# jetson_nano_breakout_rev1.net
KiCad netlist of a schematic drawn in Altium Designer
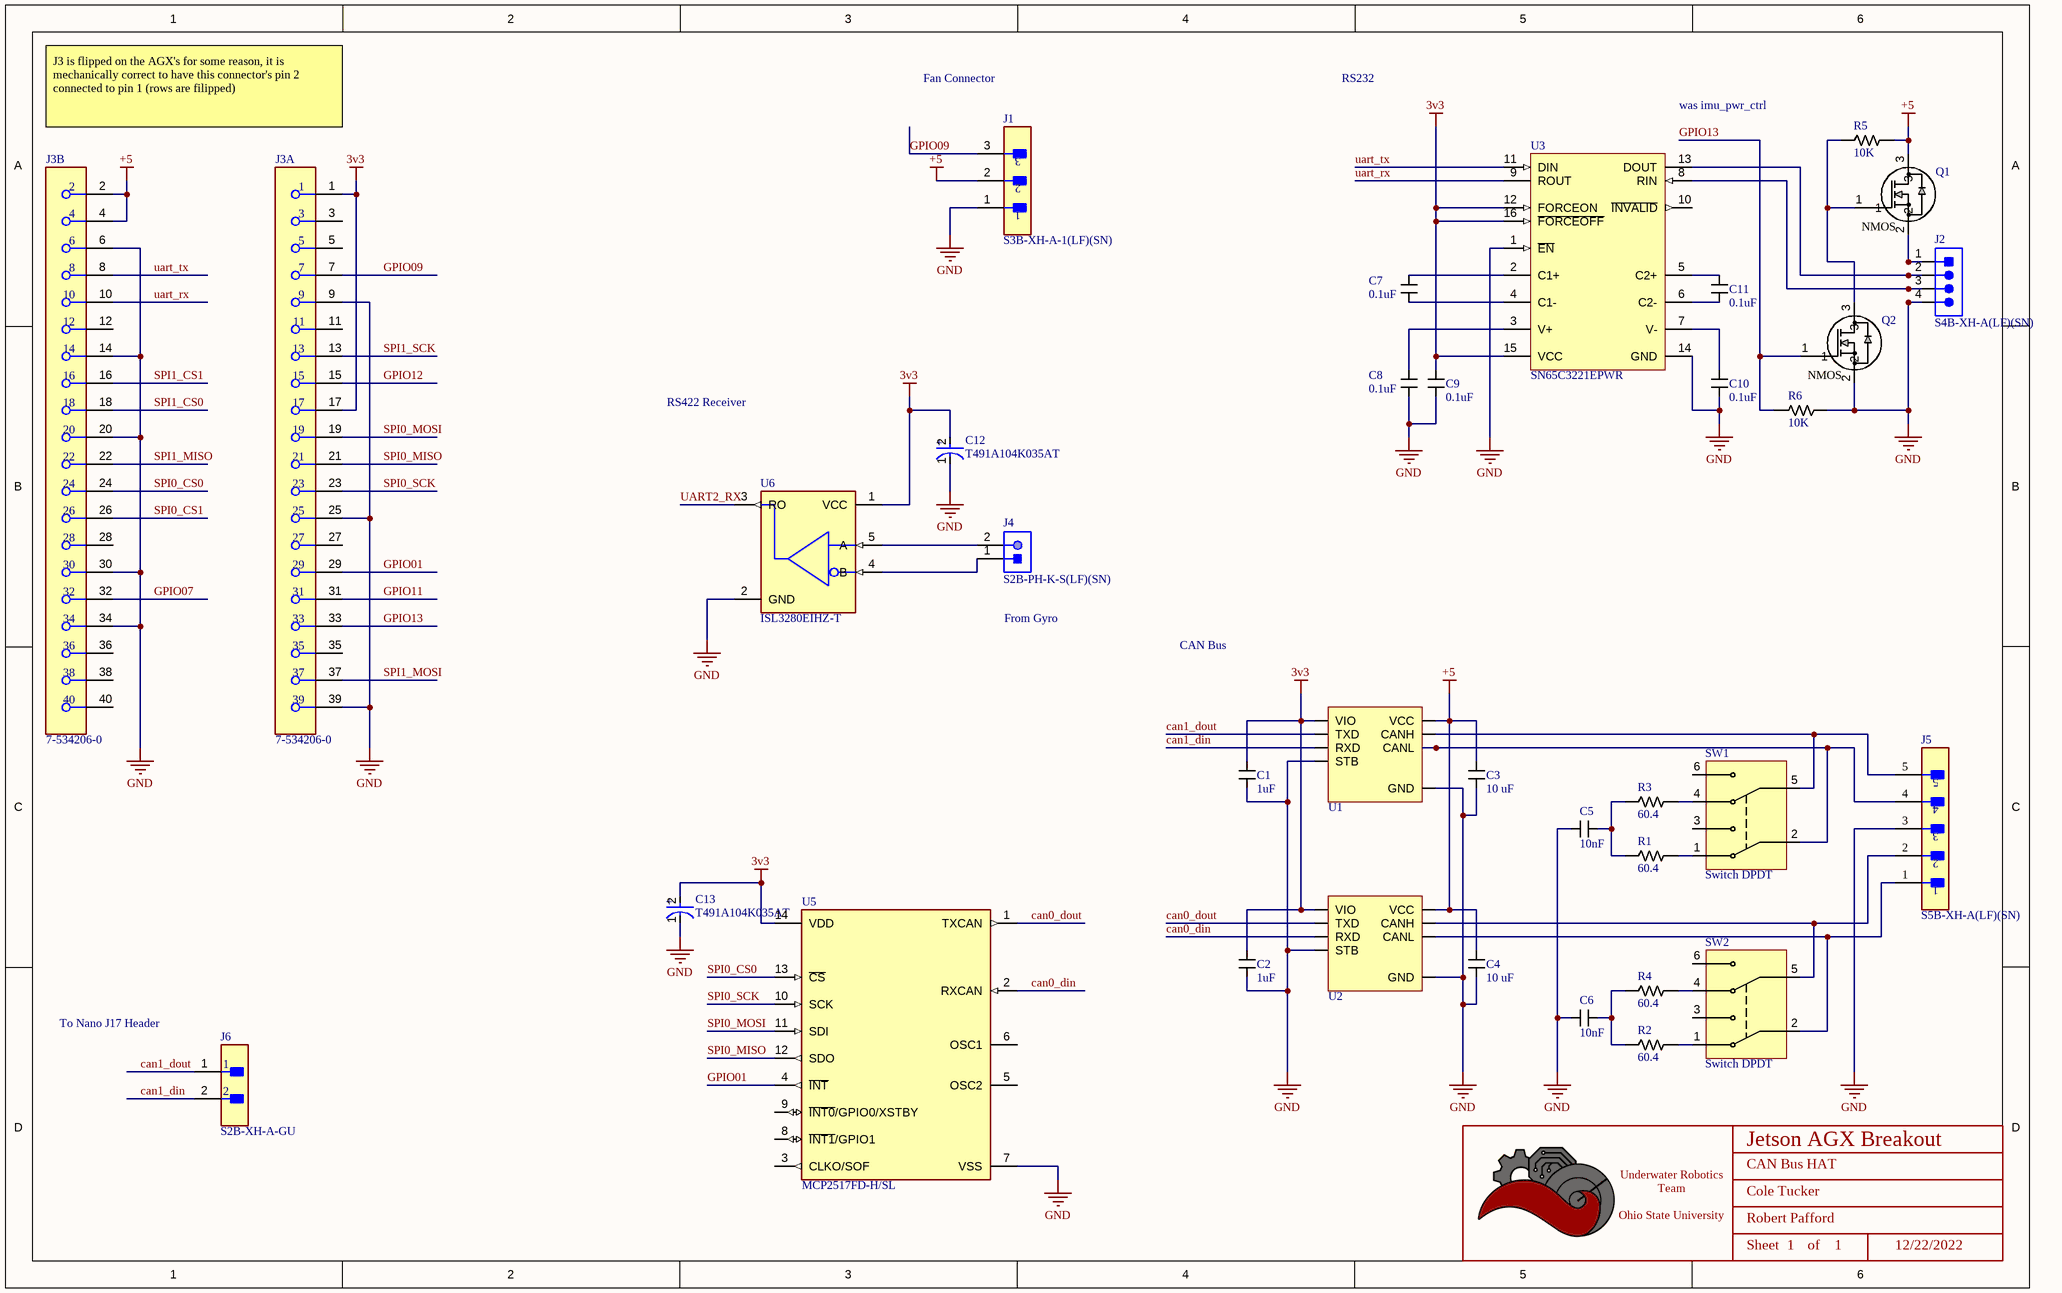
[diagram p0: jetson_nano_breakout_rev1.SchDoc]

(export (version "E")
  (design (tool "Eeschema 10.0.6"))
  (components
    (comp (ref "*")
      (value "Title_Block")
      (footprint "LOGO")
      (description "UWRT Schematic Title Block Template\r\n\r\nCreated June 2021, Dylan Trainor")
      (libsource (lib "UWRT") (part "Title_Block"))
    )
    (comp (ref "C1")
      (value "1uF")
      (footprint "CAPACITOR_0603")
      (description "Cap 1uF 16V +/-10%\r\nCeramic 0603")
      (fields
        (field (name "TOLERANCE") "+/- 10%")
        (field (name "VOLTAGE") "16V")
        (field (name "MADE BY") "Flip B")
      )
      (libsource (lib "Capacitors") (part "CAPACITOR_1uF_0603"))
    )
    (comp (ref "C2")
      (value "1uF")
      (footprint "CAPACITOR_0603")
      (description "Cap 1uF 16V +/-10%\r\nCeramic 0603")
      (fields
        (field (name "TOLERANCE") "+/- 10%")
        (field (name "VOLTAGE") "16V")
        (field (name "MADE BY") "Flip B")
      )
      (libsource (lib "Capacitors") (part "CAPACITOR_1uF_0603"))
    )
    (comp (ref "C3")
      (value "10uF Ceramic 6.3V")
      (footprint "CAPACITOR_0603")
      (description "Cap 10uF 6.3V +/-20%\r\nCeramic 0603")
      (fields
        (field (name "TOLERANCE") "+/- 20%")
        (field (name "VOLTAGE") "6.3V")
        (field (name "VALUE (UF)") "10 uF")
        (field (name "MADE BY") "Flip B")
      )
      (libsource (lib "Capacitors") (part "CAPACITOR_10uF_0603"))
    )
    (comp (ref "C4")
      (value "10uF Ceramic 6.3V")
      (footprint "CAPACITOR_0603")
      (description "Cap 10uF 6.3V +/-20%\r\nCeramic 0603")
      (fields
        (field (name "TOLERANCE") "+/- 20%")
        (field (name "VOLTAGE") "6.3V")
        (field (name "VALUE (UF)") "10 uF")
        (field (name "MADE BY") "Flip B")
      )
      (libsource (lib "Capacitors") (part "CAPACITOR_10uF_0603"))
    )
    (comp (ref "C5")
      (value "10nF")
      (footprint "CAPACITOR_0603")
      (description "Cap 10nF 6.3V +/-20%\r\nCeramic 0603")
      (fields
        (field (name "TOLERANCE") "+/- 10%")
        (field (name "VOLTAGE") "6.3V")
        (field (name "MADE BY") "Flip B")
      )
      (libsource (lib "Capacitors") (part "CAPACITOR_0.01uF_0603"))
    )
    (comp (ref "C6")
      (value "10nF")
      (footprint "CAPACITOR_0603")
      (description "Cap 10nF 6.3V +/-20%\r\nCeramic 0603")
      (fields
        (field (name "TOLERANCE") "+/- 10%")
        (field (name "VOLTAGE") "6.3V")
        (field (name "MADE BY") "Flip B")
      )
      (libsource (lib "Capacitors") (part "CAPACITOR_0.01uF_0603"))
    )
    (comp (ref "C7")
      (value "0.1uF")
      (footprint "CAPACITOR_0603")
      (description "Cap 100nF 6.3V +/-10%\r\nCeramic 0603")
      (fields
        (field (name "TOLERANCE") "+/- 10%")
        (field (name "VOLTAGE") "6.3V")
        (field (name "MADE BY") "Flip B")
      )
      (libsource (lib "Capacitors") (part "CAPACITOR_0.1uF_0603"))
    )
    (comp (ref "C8")
      (value "0.1uF")
      (footprint "CAPACITOR_0603")
      (description "Cap 100nF 6.3V +/-10%\r\nCeramic 0603")
      (fields
        (field (name "TOLERANCE") "+/- 10%")
        (field (name "VOLTAGE") "6.3V")
        (field (name "MADE BY") "Flip B")
      )
      (libsource (lib "Capacitors") (part "CAPACITOR_0.1uF_0603"))
    )
    (comp (ref "C9")
      (value "0.1uF")
      (footprint "CAPACITOR_0603")
      (description "Cap 100nF 6.3V +/-10%\r\nCeramic 0603")
      (fields
        (field (name "TOLERANCE") "+/- 10%")
        (field (name "VOLTAGE") "6.3V")
        (field (name "MADE BY") "Flip B")
      )
      (libsource (lib "Capacitors") (part "CAPACITOR_0.1uF_0603"))
    )
    (comp (ref "C10")
      (value "0.1uF")
      (footprint "CAPACITOR_0603")
      (description "Cap 100nF 6.3V +/-10%\r\nCeramic 0603")
      (fields
        (field (name "TOLERANCE") "+/- 10%")
        (field (name "VOLTAGE") "6.3V")
        (field (name "MADE BY") "Flip B")
      )
      (libsource (lib "Capacitors") (part "CAPACITOR_0.1uF_0603"))
    )
    (comp (ref "C11")
      (value "0.1uF")
      (footprint "CAPACITOR_0603")
      (description "Cap 100nF 6.3V +/-10%\r\nCeramic 0603")
      (fields
        (field (name "TOLERANCE") "+/- 10%")
        (field (name "VOLTAGE") "6.3V")
        (field (name "MADE BY") "Flip B")
      )
      (libsource (lib "Capacitors") (part "CAPACITOR_0.1uF_0603"))
    )
    (comp (ref "C12")
      (value "T491A104K035AT")
      (footprint "FP-T491A104K035AT-MFG")
      (description "CAP TANT 0.1UF 10% 35V 1206")
      (fields (field (name "TOLERANCE") "10%") (field (name "VOLTAGE") "35V"))
      (libsource (lib "Altium Content Vault") (part "a00bbbee19879c290e62620ae7e47b1"))
    )
    (comp (ref "C13")
      (value "T491A104K035AT")
      (footprint "FP-T491A104K035AT-MFG")
      (description "CAP TANT 0.1UF 10% 35V 1206")
      (fields (field (name "TOLERANCE") "10%") (field (name "VOLTAGE") "35V"))
      (libsource (lib "Altium Content Vault") (part "a00bbbee19879c290e62620ae7e47b1"))
    )
    (comp (ref "J1")
      (value "S3B-XH-A-1(LF)(SN)")
      (footprint "FP-S3B-XH-A-1_LF_SN-MFG")
      (description "CONN HEADER R/A 3POS 2.5MM")
      (libsource (lib "Altium Content Vault") (part "0d3f023dd272f625e17a2be33dea85f"))
    )
    (comp (ref "J2")
      (value "S4B-XH-A(LF)(SN)")
      (footprint "JST-S4B-XH-A(LF)(SN)_V")
      (libsource (lib "Altium Content Vault") (part "CN-1P-M-R4"))
    )
    (comp (ref "J3")
      (value "7-534206-0")
      (footprint "FP-7-534206-0-MFG")
      (description "CONN RCPT 40POS 0.1 GOLD PCB")
      (fields
        (field (name "MANUFACTURER") "TE Connectivity")
        (field (name "OCTOPART") "https://octopart.com/7-534206-0-te+connectivity-39516831")
      )
      (libsource (lib "Altium Content Vault") (part "7acf1c4a8db21028d11741a46a6ec78"))
    )
    (comp (ref "J4")
      (value "S2B-PH-K-S(LF)(SN)")
      (footprint "JST-S2B-PH-K-S_V")
      (fields (field (name "TOLERANCE") "20%"))
      (libsource (lib "Altium Content Vault") (part "CN-1P-M-R2"))
    )
    (comp (ref "J5")
      (value "S5B-XH-A(LF)(SN)")
      (footprint "FP-S5B-XH-A_LF_SN-MFG")
      (description "CONN HEADER R/A 5POS 2.5MM")
      (libsource (lib "Altium Content Vault") (part "bf93c07fd2649a848d0ec8585582aab"))
    )
    (comp (ref "J6")
      (value "S2B-XH-A-GU")
      (footprint "FP-S2B-XH-A-GU-MFG")
      (description "Conn Shrouded Header HDR 2 POS 2.45mm Solder ST Top Entry Thru-Hole")
      (libsource (lib "Altium Content Vault") (part "3bc925449376181038e59eaffc5286c"))
    )
    (comp (ref "Q1")
      (value "MOSFET N-CH 30V 5.8A SOT-23-3")
      (footprint "SOT-23-3")
      (description "N-Channel 30 V 5.8A (Ta) 1.4W (Ta) Surface Mount SOT-23-3")
      (fields (field (name "MANUFACTURER _PART_NUMBER") "AO3404A") (field (name "CREATED BY") "Dylan T"))
      (libsource (lib "Transistors") (part "AO3404A"))
    )
    (comp (ref "Q2")
      (value "MOSFET N-CH 30V 5.8A SOT-23-3")
      (footprint "SOT-23-3")
      (description "N-Channel 30 V 5.8A (Ta) 1.4W (Ta) Surface Mount SOT-23-3")
      (fields (field (name "MANUFACTURER _PART_NUMBER") "AO3404A") (field (name "CREATED BY") "Dylan T"))
      (libsource (lib "Transistors") (part "AO3404A"))
    )
    (comp (ref "R1")
      (value "60.4 Ohm 1% 1/16W")
      (footprint "RESISTOR_0402")
      (description "RES 60.4 OHM 1% 1/16W 0402")
      (fields
        (field (name "TOLERANCE") "+/- 1%")
        (field (name "VALUE  (OHMS)") "60.4")
        (field (name "MADE BY") "Robert Pafford")
      )
      (libsource (lib "Resistors") (part "RESISTOR_60.4_0402"))
    )
    (comp (ref "R2")
      (value "60.4 Ohm 1% 1/16W")
      (footprint "RESISTOR_0402")
      (description "RES 60.4 OHM 1% 1/16W 0402")
      (fields
        (field (name "TOLERANCE") "+/- 1%")
        (field (name "VALUE  (OHMS)") "60.4")
        (field (name "MADE BY") "Robert Pafford")
      )
      (libsource (lib "Resistors") (part "RESISTOR_60.4_0402"))
    )
    (comp (ref "R3")
      (value "60.4 Ohm 1% 1/16W")
      (footprint "RESISTOR_0402")
      (description "RES 60.4 OHM 1% 1/16W 0402")
      (fields
        (field (name "TOLERANCE") "+/- 1%")
        (field (name "VALUE  (OHMS)") "60.4")
        (field (name "MADE BY") "Robert Pafford")
      )
      (libsource (lib "Resistors") (part "RESISTOR_60.4_0402"))
    )
    (comp (ref "R4")
      (value "60.4 Ohm 1% 1/16W")
      (footprint "RESISTOR_0402")
      (description "RES 60.4 OHM 1% 1/16W 0402")
      (fields
        (field (name "TOLERANCE") "+/- 1%")
        (field (name "VALUE  (OHMS)") "60.4")
        (field (name "MADE BY") "Robert Pafford")
      )
      (libsource (lib "Resistors") (part "RESISTOR_60.4_0402"))
    )
    (comp (ref "R5")
      (value "10k Ohm 5% 1/10W")
      (footprint "RESISTOR_0603")
      (description "RES 10k OHM 5% 1/10W 0603")
      (fields
        (field (name "TOLERANCE") "+/- 5%")
        (field (name "VALUE  (OHMS)") "10K")
        (field (name "MADE BY") "Robert Pafford")
      )
      (libsource (lib "Resistors") (part "RESISTOR_10K_0603"))
    )
    (comp (ref "R6")
      (value "10k Ohm 5% 1/10W")
      (footprint "RESISTOR_0603")
      (description "RES 10k OHM 5% 1/10W 0603")
      (fields
        (field (name "TOLERANCE") "+/- 5%")
        (field (name "VALUE  (OHMS)") "10K")
        (field (name "MADE BY") "Robert Pafford")
      )
      (libsource (lib "Resistors") (part "RESISTOR_10K_0603"))
    )
    (comp (ref "SW1")
      (value "Switch DPDT")
      (footprint "CAS-220TA")
      (description "GOLD SWITCH FLUSH SLIDE DPDT 100MA 6V")
      (fields (field (name "MADE BY") "Robert Pafford"))
      (libsource (lib "Switches") (part "CAS-220TA_CAN_TERM"))
    )
    (comp (ref "SW2")
      (value "Switch DPDT")
      (footprint "CAS-220TA")
      (description "GOLD SWITCH FLUSH SLIDE DPDT 100MA 6V")
      (fields (field (name "MADE BY") "Robert Pafford"))
      (libsource (lib "Switches") (part "CAS-220TA_CAN_TERM"))
    )
    (comp (ref "U1")
      (value "CAN Transceiver")
      (footprint "SOIC-8")
      (description "CAN Interface IC High-Speed CAN Transceiver with Standby Mode")
      (fields (field (name "MADE BY") "Robert Pafford"))
      (libsource (lib "Integrated Circuits") (part "TJA1442AT"))
    )
    (comp (ref "U2")
      (value "CAN Transceiver")
      (footprint "SOIC-8")
      (description "CAN Interface IC High-Speed CAN Transceiver with Standby Mode")
      (fields (field (name "MADE BY") "Robert Pafford"))
      (libsource (lib "Integrated Circuits") (part "TJA1442AT"))
    )
    (comp (ref "U3")
      (value "SN65C3221EPWR")
      (footprint "PW0016A_M")
      (libsource (lib "Altium Content Vault") (part "TI-SN65C3221E-TSSOP_PW-16"))
    )
    (comp (ref "U5")
      (value "MCP2517FD-H/SL")
      (footprint "FP-C04-065-SL-MFG")
      (description "IC CANBUS CONTROLLER SPI 14SOIC")
      (fields
        (field (name "MANUFACTURER") "Microchip")
        (field (name "OCTOPART") "https://octopart.com/mcp2517fd-h%2Fsl-microchip-83497369")
      )
      (libsource (lib "Altium Content Vault") (part "008caafe10a874835a82fe443bcfa61"))
    )
    (comp (ref "U6")
      (value "ISL3280EIHZ-T")
      (footprint "FP-P5_064-MFG")
      (description "IC RCVR ESD RS485/422 LP SOT23-5")
      (fields
        (field (name "MANUFACTURER") "Renesas")
        (field (name "OCTOPART") "https://octopart.com/isl3280eihz-t-renesas-88254858")
      )
      (libsource (lib "Altium Content Vault") (part "dfcd02365d4109d45b3bc98e27c58b4"))
    )
  )
  (nets
    (net (code "1") (name "+5") (class "Default")
      (node (ref "C3") (pin "1") (pinfunction "1_1") (pintype "passive"))
      (node (ref "C4") (pin "1") (pinfunction "1_1") (pintype "passive"))
      (node (ref "J1") (pin "2") (pinfunction "2_2") (pintype "passive"))
      (node (ref "J3") (pin "2") (pinfunction "2_2") (pintype "passive"))
      (node (ref "J3") (pin "4") (pinfunction "4_4") (pintype "passive"))
      (node (ref "Q1") (pin "3") (pinfunction "3_3") (pintype "passive"))
      (node (ref "R5") (pin "1") (pinfunction "1_1") (pintype "passive"))
      (node (ref "U1") (pin "3") (pinfunction "VCC_3") (pintype "passive"))
      (node (ref "U2") (pin "3") (pinfunction "VCC_3") (pintype "passive"))
    )
    (net (code "2") (name "/GPIO01") (class "Default")
      (node (ref "J3") (pin "29") (pinfunction "29_29") (pintype "passive"))
      (node (ref "U5") (pin "4") (pinfunction "~{INT}_4") (pintype "output"))
    )
    (net (code "3") (name "/GPIO07") (class "Default")
      (node (ref "J3") (pin "32") (pinfunction "32_32") (pintype "passive"))
    )
    (net (code "4") (name "/GPIO09") (class "Default")
      (node (ref "J1") (pin "3") (pinfunction "3_3") (pintype "passive"))
      (node (ref "J3") (pin "7") (pinfunction "7_7") (pintype "passive"))
    )
    (net (code "5") (name "/GPIO11") (class "Default")
      (node (ref "J3") (pin "31") (pinfunction "31_31") (pintype "passive"))
    )
    (net (code "6") (name "/GPIO12") (class "Default")
      (node (ref "J3") (pin "15") (pinfunction "15_15") (pintype "passive"))
    )
    (net (code "7") (name "/GPIO13") (class "Default")
      (node (ref "J3") (pin "33") (pinfunction "33_33") (pintype "passive"))
      (node (ref "Q2") (pin "1") (pinfunction "1_1") (pintype "passive"))
      (node (ref "R6") (pin "1") (pinfunction "1_1") (pintype "passive"))
    )
    (net (code "8") (name "/SPI0_CS0") (class "Default")
      (node (ref "J3") (pin "24") (pinfunction "24_24") (pintype "passive"))
      (node (ref "U5") (pin "13") (pinfunction "~{CS}_13") (pintype "input"))
    )
    (net (code "9") (name "/SPI0_CS1") (class "Default")
      (node (ref "J3") (pin "26") (pinfunction "26_26") (pintype "passive"))
    )
    (net (code "10") (name "/SPI0_MISO") (class "Default")
      (node (ref "J3") (pin "21") (pinfunction "21_21") (pintype "passive"))
      (node (ref "U5") (pin "12") (pinfunction "SDO_12") (pintype "output"))
    )
    (net (code "11") (name "/SPI0_MOSI") (class "Default")
      (node (ref "J3") (pin "19") (pinfunction "19_19") (pintype "passive"))
      (node (ref "U5") (pin "11") (pinfunction "SDI_11") (pintype "input"))
    )
    (net (code "12") (name "/SPI0_SCK") (class "Default")
      (node (ref "J3") (pin "23") (pinfunction "23_23") (pintype "passive"))
      (node (ref "U5") (pin "10") (pinfunction "SCK_10") (pintype "input"))
    )
    (net (code "13") (name "/SPI1_CS0") (class "Default")
      (node (ref "J3") (pin "18") (pinfunction "18_18") (pintype "passive"))
    )
    (net (code "14") (name "/SPI1_CS1") (class "Default")
      (node (ref "J3") (pin "16") (pinfunction "16_16") (pintype "passive"))
    )
    (net (code "15") (name "/SPI1_MISO") (class "Default")
      (node (ref "J3") (pin "22") (pinfunction "22_22") (pintype "passive"))
    )
    (net (code "16") (name "/SPI1_MOSI") (class "Default")
      (node (ref "J3") (pin "37") (pinfunction "37_37") (pintype "passive"))
    )
    (net (code "17") (name "/SPI1_SCK") (class "Default")
      (node (ref "J3") (pin "13") (pinfunction "13_13") (pintype "passive"))
    )
    (net (code "18") (name "/UART2_RX") (class "Default")
      (node (ref "U6") (pin "3") (pinfunction "RO_3") (pintype "output"))
    )
    (net (code "19") (name "/can0_din") (class "Default")
      (node (ref "U2") (pin "4") (pinfunction "RXD_4") (pintype "passive"))
      (node (ref "U5") (pin "2") (pinfunction "RXCAN_2") (pintype "input"))
    )
    (net (code "20") (name "/can0_dout") (class "Default")
      (node (ref "U2") (pin "1") (pinfunction "TXD_1") (pintype "passive"))
      (node (ref "U5") (pin "1") (pinfunction "TXCAN_1") (pintype "output"))
    )
    (net (code "21") (name "/can1_din") (class "Default")
      (node (ref "J6") (pin "2") (pinfunction "2_2") (pintype "passive"))
      (node (ref "U1") (pin "4") (pinfunction "RXD_4") (pintype "passive"))
    )
    (net (code "22") (name "/can1_dout") (class "Default")
      (node (ref "J6") (pin "1") (pinfunction "1_1") (pintype "passive"))
      (node (ref "U1") (pin "1") (pinfunction "TXD_1") (pintype "passive"))
    )
    (net (code "23") (name "/uart_rx") (class "Default")
      (node (ref "J3") (pin "10") (pinfunction "10_10") (pintype "passive"))
      (node (ref "U3") (pin "9") (pinfunction "ROUT_9") (pintype "tri_state"))
    )
    (net (code "24") (name "/uart_tx") (class "Default")
      (node (ref "J3") (pin "8") (pinfunction "8_8") (pintype "passive"))
      (node (ref "U3") (pin "11") (pinfunction "DIN_11") (pintype "input"))
    )
    (net (code "25") (name "3v3") (class "Default")
      (node (ref "C1") (pin "1") (pinfunction "1_1") (pintype "passive"))
      (node (ref "C12") (pin "2") (pinfunction "A_2") (pintype "passive"))
      (node (ref "C13") (pin "2") (pinfunction "A_2") (pintype "passive"))
      (node (ref "C2") (pin "1") (pinfunction "1_1") (pintype "passive"))
      (node (ref "C9") (pin "1") (pinfunction "1_1") (pintype "passive"))
      (node (ref "J3") (pin "1") (pinfunction "1_1") (pintype "passive"))
      (node (ref "J3") (pin "17") (pinfunction "17_17") (pintype "passive"))
      (node (ref "U1") (pin "5") (pinfunction "VIO_5") (pintype "passive"))
      (node (ref "U2") (pin "5") (pinfunction "VIO_5") (pintype "passive"))
      (node (ref "U3") (pin "12") (pinfunction "FORCEON_12") (pintype "input"))
      (node (ref "U3") (pin "15") (pinfunction "VCC_15") (pintype "power_in"))
      (node (ref "U3") (pin "16") (pinfunction "~{FORCEOFF}_16") (pintype "input"))
      (node (ref "U5") (pin "14") (pinfunction "VDD_14") (pintype "power_in"))
      (node (ref "U6") (pin "1") (pinfunction "VCC_1") (pintype "power_in"))
    )
    (net (code "26") (name "GND") (class "Default")
      (node (ref "C1") (pin "2") (pinfunction "2_2") (pintype "passive"))
      (node (ref "C10") (pin "2") (pinfunction "2_2") (pintype "passive"))
      (node (ref "C12") (pin "1") (pinfunction "C_1") (pintype "passive"))
      (node (ref "C13") (pin "1") (pinfunction "C_1") (pintype "passive"))
      (node (ref "C2") (pin "2") (pinfunction "2_2") (pintype "passive"))
      (node (ref "C3") (pin "2") (pinfunction "2_2") (pintype "passive"))
      (node (ref "C4") (pin "2") (pinfunction "2_2") (pintype "passive"))
      (node (ref "C5") (pin "1") (pinfunction "1_1") (pintype "passive"))
      (node (ref "C6") (pin "1") (pinfunction "1_1") (pintype "passive"))
      (node (ref "C8") (pin "2") (pinfunction "2_2") (pintype "passive"))
      (node (ref "C9") (pin "2") (pinfunction "2_2") (pintype "passive"))
      (node (ref "J1") (pin "1") (pinfunction "1_1") (pintype "passive"))
      (node (ref "J2") (pin "4") (pinfunction "4_4") (pintype "passive"))
      (node (ref "J3") (pin "14") (pinfunction "14_14") (pintype "passive"))
      (node (ref "J3") (pin "20") (pinfunction "20_20") (pintype "passive"))
      (node (ref "J3") (pin "25") (pinfunction "25_25") (pintype "passive"))
      (node (ref "J3") (pin "30") (pinfunction "30_30") (pintype "passive"))
      (node (ref "J3") (pin "34") (pinfunction "34_34") (pintype "passive"))
      (node (ref "J3") (pin "39") (pinfunction "39_39") (pintype "passive"))
      (node (ref "J3") (pin "6") (pinfunction "6_6") (pintype "passive"))
      (node (ref "J3") (pin "9") (pinfunction "9_9") (pintype "passive"))
      (node (ref "J5") (pin "3") (pinfunction "3_3") (pintype "passive"))
      (node (ref "Q2") (pin "2") (pinfunction "2_2") (pintype "passive"))
      (node (ref "R6") (pin "2") (pinfunction "2_2") (pintype "passive"))
      (node (ref "U1") (pin "2") (pinfunction "GND_2") (pintype "passive"))
      (node (ref "U1") (pin "8") (pinfunction "STB_8") (pintype "passive"))
      (node (ref "U2") (pin "2") (pinfunction "GND_2") (pintype "passive"))
      (node (ref "U2") (pin "8") (pinfunction "STB_8") (pintype "passive"))
      (node (ref "U3") (pin "1") (pinfunction "~{EN}_1") (pintype "input"))
      (node (ref "U3") (pin "14") (pinfunction "GND_14") (pintype "power_in"))
      (node (ref "U5") (pin "7") (pinfunction "VSS_7") (pintype "power_in"))
      (node (ref "U6") (pin "2") (pinfunction "GND_2") (pintype "power_in"))
    )
    (net (code "27") (name "Net-(C5-Pad2)") (class "Default")
      (node (ref "C5") (pin "2") (pinfunction "2_2") (pintype "passive"))
      (node (ref "R1") (pin "2") (pinfunction "2_2") (pintype "passive"))
      (node (ref "R3") (pin "2") (pinfunction "2_2") (pintype "passive"))
    )
    (net (code "28") (name "Net-(C6-Pad2)") (class "Default")
      (node (ref "C6") (pin "2") (pinfunction "2_2") (pintype "passive"))
      (node (ref "R2") (pin "2") (pinfunction "2_2") (pintype "passive"))
      (node (ref "R4") (pin "2") (pinfunction "2_2") (pintype "passive"))
    )
    (net (code "29") (name "Net-(J2-Pad1)") (class "Default")
      (node (ref "J2") (pin "1") (pinfunction "1_1") (pintype "passive"))
      (node (ref "Q1") (pin "2") (pinfunction "2_2") (pintype "passive"))
    )
    (net (code "30") (name "Net-(Q1-Pad1)") (class "Default")
      (node (ref "Q1") (pin "1") (pinfunction "1_1") (pintype "passive"))
      (node (ref "Q2") (pin "3") (pinfunction "3_3") (pintype "passive"))
      (node (ref "R5") (pin "2") (pinfunction "2_2") (pintype "passive"))
    )
    (net (code "31") (name "Net-(R1-Pad1)") (class "Default")
      (node (ref "R1") (pin "1") (pinfunction "1_1") (pintype "passive"))
      (node (ref "SW1") (pin "1") (pintype "passive"))
    )
    (net (code "32") (name "Net-(R2-Pad1)") (class "Default")
      (node (ref "R2") (pin "1") (pinfunction "1_1") (pintype "passive"))
      (node (ref "SW2") (pin "1") (pintype "passive"))
    )
    (net (code "33") (name "Net-(R3-Pad1)") (class "Default")
      (node (ref "R3") (pin "1") (pinfunction "1_1") (pintype "passive"))
      (node (ref "SW1") (pin "4") (pintype "passive"))
    )
    (net (code "34") (name "Net-(R4-Pad1)") (class "Default")
      (node (ref "R4") (pin "1") (pinfunction "1_1") (pintype "passive"))
      (node (ref "SW2") (pin "4") (pintype "passive"))
    )
    (net (code "35") (name "Net-(U1-CANH)") (class "Default")
      (node (ref "J5") (pin "5") (pinfunction "5_5") (pintype "passive"))
      (node (ref "SW1") (pin "5") (pintype "passive"))
      (node (ref "U1") (pin "7") (pinfunction "CANH_7") (pintype "passive"))
    )
    (net (code "36") (name "Net-(U1-CANL)") (class "Default")
      (node (ref "J5") (pin "4") (pinfunction "4_4") (pintype "passive"))
      (node (ref "SW1") (pin "2") (pintype "passive"))
      (node (ref "U1") (pin "6") (pinfunction "CANL_6") (pintype "passive"))
    )
    (net (code "37") (name "Net-(U2-CANH)") (class "Default")
      (node (ref "J5") (pin "2") (pinfunction "2_2") (pintype "passive"))
      (node (ref "SW2") (pin "5") (pintype "passive"))
      (node (ref "U2") (pin "7") (pinfunction "CANH_7") (pintype "passive"))
    )
    (net (code "38") (name "Net-(U2-CANL)") (class "Default")
      (node (ref "J5") (pin "1") (pinfunction "1_1") (pintype "passive"))
      (node (ref "SW2") (pin "2") (pintype "passive"))
      (node (ref "U2") (pin "6") (pinfunction "CANL_6") (pintype "passive"))
    )
    (net (code "39") (name "Net-(U3-C1+)") (class "Default")
      (node (ref "C7") (pin "1") (pinfunction "1_1") (pintype "passive"))
      (node (ref "U3") (pin "2") (pinfunction "C1+_2") (pintype "passive"))
    )
    (net (code "40") (name "Net-(U3-C1-)") (class "Default")
      (node (ref "C7") (pin "2") (pinfunction "2_2") (pintype "passive"))
      (node (ref "U3") (pin "4") (pinfunction "C1-_4") (pintype "passive"))
    )
    (net (code "41") (name "Net-(U3-C2+)") (class "Default")
      (node (ref "C11") (pin "1") (pinfunction "1_1") (pintype "passive"))
      (node (ref "U3") (pin "5") (pinfunction "C2+_5") (pintype "passive"))
    )
    (net (code "42") (name "Net-(U3-C2-)") (class "Default")
      (node (ref "C11") (pin "2") (pinfunction "2_2") (pintype "passive"))
      (node (ref "U3") (pin "6") (pinfunction "C2-_6") (pintype "passive"))
    )
    (net (code "43") (name "Net-(U3-DOUT)") (class "Default")
      (node (ref "J2") (pin "2") (pinfunction "2_2") (pintype "passive"))
      (node (ref "U3") (pin "13") (pinfunction "DOUT_13") (pintype "tri_state"))
    )
    (net (code "44") (name "Net-(U3-RIN)") (class "Default")
      (node (ref "J2") (pin "3") (pinfunction "3_3") (pintype "passive"))
      (node (ref "U3") (pin "8") (pinfunction "RIN_8") (pintype "input"))
    )
    (net (code "45") (name "Net-(U3-V+)") (class "Default")
      (node (ref "C8") (pin "1") (pinfunction "1_1") (pintype "passive"))
      (node (ref "U3") (pin "3") (pinfunction "V+_3") (pintype "power_in"))
    )
    (net (code "46") (name "Net-(U3-V-)") (class "Default")
      (node (ref "C10") (pin "1") (pinfunction "1_1") (pintype "passive"))
      (node (ref "U3") (pin "7") (pinfunction "V-_7") (pintype "power_in"))
    )
    (net (code "47") (name "Net-(U6-A)") (class "Default")
      (node (ref "J4") (pin "2") (pinfunction "2_2") (pintype "passive"))
      (node (ref "U6") (pin "5") (pinfunction "A_5") (pintype "input"))
    )
    (net (code "48") (name "Net-(U6-B)") (class "Default")
      (node (ref "J4") (pin "1") (pinfunction "1_1") (pintype "passive"))
      (node (ref "U6") (pin "4") (pinfunction "B_4") (pintype "input"))
    )
    (net (code "49") (name "unconnected-(J3-Pad3)") (class "Default")
      (node (ref "J3") (pin "3") (pinfunction "3_3") (pintype "passive"))
    )
    (net (code "50") (name "unconnected-(J3-Pad5)") (class "Default")
      (node (ref "J3") (pin "5") (pinfunction "5_5") (pintype "passive"))
    )
    (net (code "51") (name "unconnected-(J3-Pad11)") (class "Default")
      (node (ref "J3") (pin "11") (pinfunction "11_11") (pintype "passive"))
    )
    (net (code "52") (name "unconnected-(J3-Pad12)") (class "Default")
      (node (ref "J3") (pin "12") (pinfunction "12_12") (pintype "passive"))
    )
    (net (code "53") (name "unconnected-(J3-Pad27)") (class "Default")
      (node (ref "J3") (pin "27") (pinfunction "27_27") (pintype "passive"))
    )
    (net (code "54") (name "unconnected-(J3-Pad28)") (class "Default")
      (node (ref "J3") (pin "28") (pinfunction "28_28") (pintype "passive"))
    )
    (net (code "55") (name "unconnected-(J3-Pad35)") (class "Default")
      (node (ref "J3") (pin "35") (pinfunction "35_35") (pintype "passive"))
    )
    (net (code "56") (name "unconnected-(J3-Pad36)") (class "Default")
      (node (ref "J3") (pin "36") (pinfunction "36_36") (pintype "passive"))
    )
    (net (code "57") (name "unconnected-(J3-Pad38)") (class "Default")
      (node (ref "J3") (pin "38") (pinfunction "38_38") (pintype "passive"))
    )
    (net (code "58") (name "unconnected-(J3-Pad40)") (class "Default")
      (node (ref "J3") (pin "40") (pinfunction "40_40") (pintype "passive"))
    )
    (net (code "59") (name "unconnected-(SW1-Pad3)") (class "Default")
      (node (ref "SW1") (pin "3") (pintype "passive"))
    )
    (net (code "60") (name "unconnected-(SW1-Pad6)") (class "Default")
      (node (ref "SW1") (pin "6") (pintype "passive"))
    )
    (net (code "61") (name "unconnected-(SW2-Pad3)") (class "Default")
      (node (ref "SW2") (pin "3") (pintype "passive"))
    )
    (net (code "62") (name "unconnected-(SW2-Pad6)") (class "Default")
      (node (ref "SW2") (pin "6") (pintype "passive"))
    )
    (net (code "63") (name "unconnected-(U3-~{INVALID}-Pad10)") (class "Default")
      (node (ref "U3") (pin "10") (pinfunction "~{INVALID}_10") (pintype "output"))
    )
    (net (code "64") (name "unconnected-(U5-CLKO{slash}SOF-Pad3)") (class "Default")
      (node (ref "U5") (pin "3") (pinfunction "CLKO/SOF_3") (pintype "output"))
    )
    (net (code "65") (name "unconnected-(U5-OSC1-Pad6)") (class "Default")
      (node (ref "U5") (pin "6") (pinfunction "OSC1_6") (pintype "passive"))
    )
    (net (code "66") (name "unconnected-(U5-OSC2-Pad5)") (class "Default")
      (node (ref "U5") (pin "5") (pinfunction "OSC2_5") (pintype "passive"))
    )
    (net (code "67") (name "unconnected-(U5-~{INT0}{slash}GPIO0{slash}XSTBY-Pad9)") (class "Default")
      (node (ref "U5") (pin "9") (pinfunction "~{INT0}/GPIO0/XSTBY_9") (pintype "bidirectional"))
    )
    (net (code "68") (name "unconnected-(U5-~{INT1}{slash}GPIO1-Pad8)") (class "Default")
      (node (ref "U5") (pin "8") (pinfunction "~{INT1}/GPIO1_8") (pintype "bidirectional"))
    )
  )
)
